# hbridgeA.net
KiCad netlist of a schematic drawn in Altium Designer
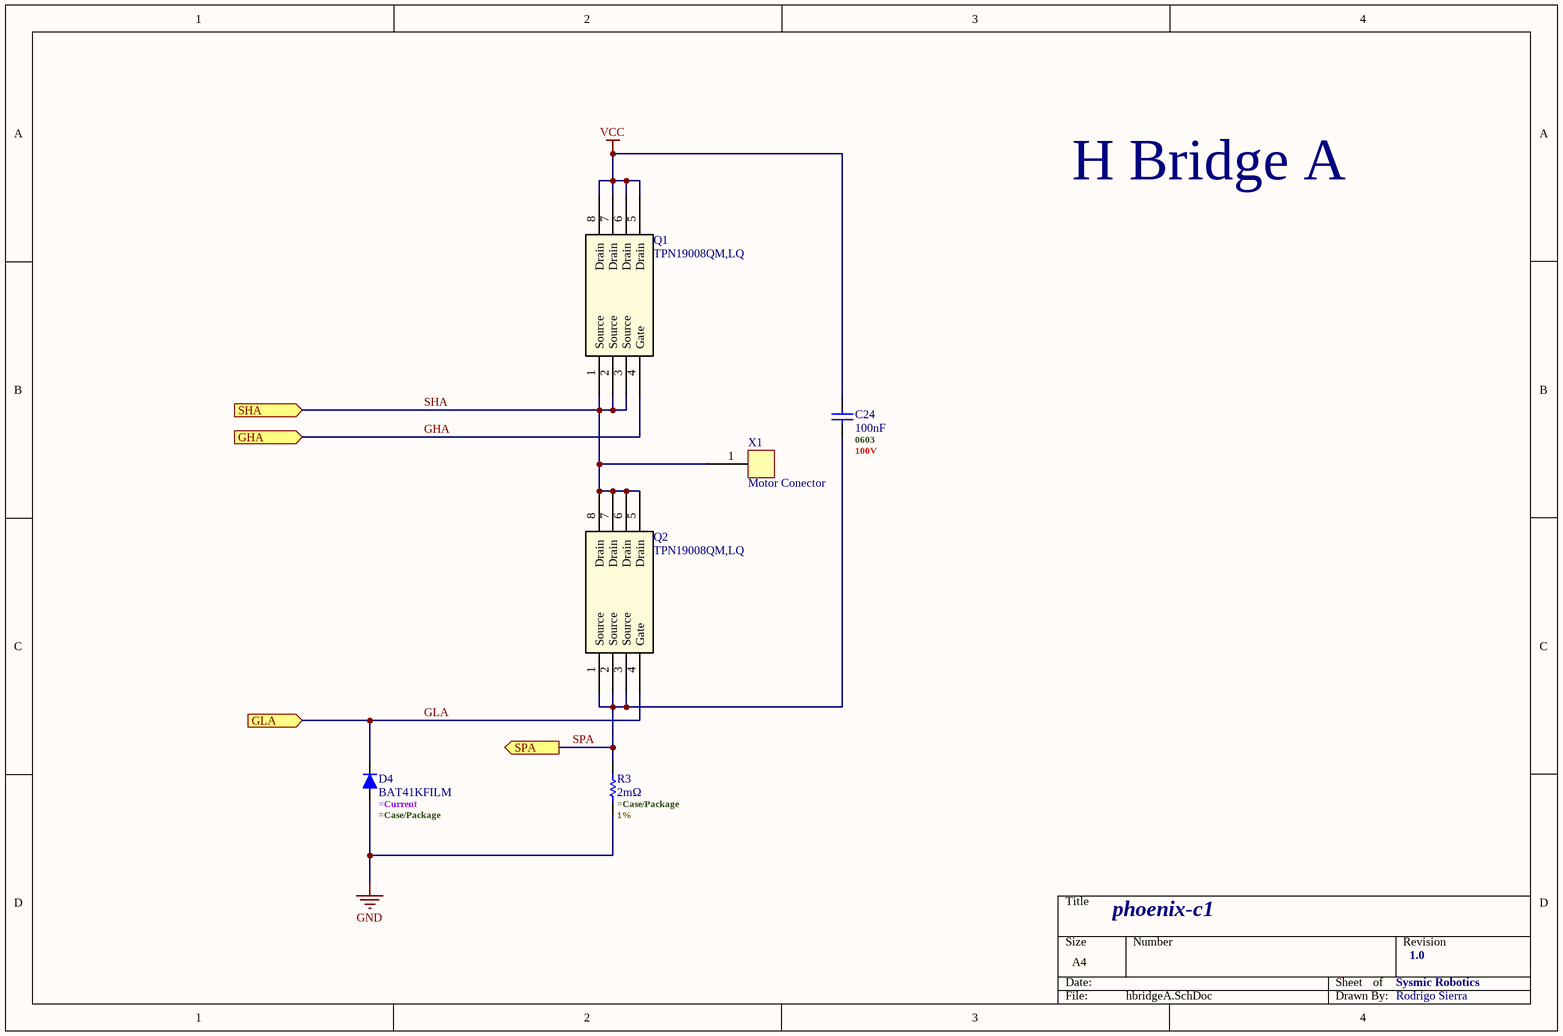
[diagram p0: hbridgeA.SchDoc]

(export (version "E")
  (design (tool "Eeschema 10.0.6"))
  (components
    (comp (ref "C24")
      (value "100nF")
      (footprint "C0603 - MURATA")
      (description "Cap Ceramic 0.1uF 100V X7R 10% Pad SMD 0603 Soft Termination 125C Automotive T/R")
      (fields
        (field (name "MANUFACTURER") "Murata")
        (field (name "MANUFACTURER PART NUMBER") "GCJ188R72A104KA01D")
        (field (name ".CASE/PACKAGE") "0603")
        (field (name ".VOLTAGE RATING (DC)") "100V")
      )
      (libsource (lib "CAP - GCJ188R72A104KA01D") (part "GCJ188R72A104KA01D"))
    )
    (comp (ref "D4")
      (value "BAT41KFILM")
      (footprint "DSOD-523 - STMicroelectronics")
      (description "Low Capacitance Small Signal 200 mA 1 V Schottky Diode Surface Mount - SOD-523")
      (fields (field (name "MANUFACTURER") "STMicroelectronics"))
      (libsource (lib "DIODE - BAT41KFILM") (part "BAT41KFILM"))
    )
    (comp (ref "Q1")
      (value "TPN19008QM,LQ")
      (footprint "8-TSON - TOSHIBA")
      (description "Power MOSFET, N Channel, 80 V, 38 A, 0.0147 ohm, TSON, Surface Mount")
      (fields (field (name "COPYRIGHT") "Copyright (C) 2025 Ultra Librarian. All rights reserved."))
      (libsource (lib "MOSFET - TPN19008QM_LQ") (part "TPN19008QM,LQ"))
    )
    (comp (ref "Q2")
      (value "TPN19008QM,LQ")
      (footprint "8-TSON - TOSHIBA")
      (description "Power MOSFET, N Channel, 80 V, 38 A, 0.0147 ohm, TSON, Surface Mount")
      (fields (field (name "COPYRIGHT") "Copyright (C) 2025 Ultra Librarian. All rights reserved."))
      (libsource (lib "MOSFET - TPN19008QM_LQ") (part "TPN19008QM,LQ"))
    )
    (comp (ref "R3")
      (value "2mΩ")
      (footprint "R0805 - SEI")
      (description "Res Metal Alloy 0805 0.002 Ohm 1% 1W ±75ppm/C Pad SMD T/R Automotive AEC-Q200")
      (fields
        (field (name "MANUFACTURER") "Stackpole Electronics")
        (field (name "MANUFACTURER PART NUMBER") "CSSH0805FT2L00")
        (field (name ".TOLERANCE") "1%")
      )
      (libsource (lib "RES - CSSH0805FT2L00") (part "CSSH0805FT2L00"))
    )
    (comp (ref "X1")
      (value "Motor Conector")
      (footprint "CONN_PHASE01x01")
      (description "Generic connector, single row")
      (libsource (lib "CONN - MOTOR PHASE") (part "Conn_01x01"))
    )
  )
  (nets
    (net (code "1") (name "/GHA") (class "Default")
      (node (ref "Q1") (pin "4") (pinfunction "Gate_4") (pintype "passive"))
    )
    (net (code "2") (name "/GLA") (class "Default")
      (node (ref "D4") (pin "1") (pinfunction "1_1") (pintype "passive"))
      (node (ref "Q2") (pin "4") (pinfunction "Gate_4") (pintype "passive"))
    )
    (net (code "3") (name "/SHA") (class "Default")
      (node (ref "Q1") (pin "1") (pinfunction "Source_1") (pintype "passive"))
      (node (ref "Q1") (pin "2") (pinfunction "Source_2") (pintype "passive"))
      (node (ref "Q1") (pin "3") (pinfunction "Source_3") (pintype "passive"))
      (node (ref "Q2") (pin "5") (pinfunction "Drain_5") (pintype "passive"))
      (node (ref "Q2") (pin "6") (pinfunction "Drain_6") (pintype "passive"))
      (node (ref "Q2") (pin "7") (pinfunction "Drain_7") (pintype "passive"))
      (node (ref "Q2") (pin "8") (pinfunction "Drain_8") (pintype "passive"))
      (node (ref "X1") (pin "1") (pinfunction "Conn_1") (pintype "passive"))
    )
    (net (code "4") (name "/SPA") (class "Default")
      (node (ref "C24") (pin "1") (pinfunction "1_1") (pintype "passive"))
      (node (ref "Q2") (pin "1") (pinfunction "Source_1") (pintype "passive"))
      (node (ref "Q2") (pin "2") (pinfunction "Source_2") (pintype "passive"))
      (node (ref "Q2") (pin "3") (pinfunction "Source_3") (pintype "passive"))
      (node (ref "R3") (pin "2") (pinfunction "2_2") (pintype "passive"))
    )
    (net (code "5") (name "GND") (class "Default")
      (node (ref "D4") (pin "2") (pinfunction "2_2") (pintype "passive"))
      (node (ref "R3") (pin "1") (pinfunction "1_1") (pintype "passive"))
    )
    (net (code "6") (name "VCC") (class "Default")
      (node (ref "C24") (pin "2") (pinfunction "2_2") (pintype "passive"))
      (node (ref "Q1") (pin "5") (pinfunction "Drain_5") (pintype "passive"))
      (node (ref "Q1") (pin "6") (pinfunction "Drain_6") (pintype "passive"))
      (node (ref "Q1") (pin "7") (pinfunction "Drain_7") (pintype "passive"))
      (node (ref "Q1") (pin "8") (pinfunction "Drain_8") (pintype "passive"))
    )
  )
)
